# gps.net
KiCad netlist of a schematic drawn in Altium Designer
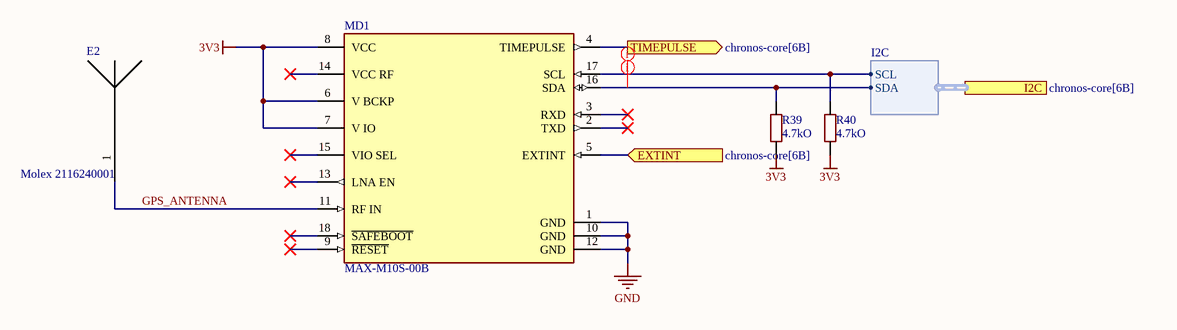
[diagram p0: gps.SchDoc]

(export (version "E")
  (design (tool "Eeschema 10.0.6"))
  (components
    (comp (ref "E2")
      (value "Molex 2116240001")
      (footprint "Molex_GPS_L1_L5_GLONASS_36MM_STACKED_2116240001")
      (libsource (lib "Molex_GPS_L1_L5_GLONASS_36MM_STACKED_2116240001") (part "Molex_GPS_L1_L5_GLONASS_36MM_STACKED_2116240001"))
    )
    (comp (ref "MD1")
      (value "MAX-M10S-00B")
      (footprint "FP-MAX-M10S-00B-MFG")
      (description "GNSS LCC RX, ROM, TCXO, LNA, SAW")
      (libsource (lib "Altium Content Vault") (part "a308a25f00fc71354910191737d199d"))
    )
    (comp (ref "R39")
      (value "4.7kO")
      (footprint "0402WGF4701TCE")
      (fields
        (field (name "JLCPCB PART #") "C25900")
        (field (name "MANUFACTURER PART NUMBER") "0402WGF4701TCE")
        (field (name "MANUFACTURER") "UNI-ROYAL(Uniroyal Elec)")
      )
      (libsource (lib "0402WGF4701TCE") (part "0402WGF4701TCE"))
    )
    (comp (ref "R40")
      (value "4.7kO")
      (footprint "0402WGF4701TCE")
      (fields
        (field (name "JLCPCB PART #") "C25900")
        (field (name "MANUFACTURER PART NUMBER") "0402WGF4701TCE")
        (field (name "MANUFACTURER") "UNI-ROYAL(Uniroyal Elec)")
      )
      (libsource (lib "0402WGF4701TCE") (part "0402WGF4701TCE"))
    )
  )
  (nets
    (net (code "2") (name "/EXTINT") (class "Default")
      (node (ref "MD1") (pin "5") (pinfunction "EXTINT_5") (pintype "input"))
    )
    (net (code "3") (name "/GPS_ANTENNA") (class "Default")
      (node (ref "E2") (pin "1") (pinfunction "ANT_1") (pintype "passive"))
      (node (ref "MD1") (pin "11") (pinfunction "RF_IN_11") (pintype "input"))
    )
    (net (code "4") (name "/TIMEPULSE") (class "Default")
      (node (ref "MD1") (pin "4") (pinfunction "TIMEPULSE_4") (pintype "output"))
    )
    (net (code "6") (name "3V3") (class "Default")
      (node (ref "MD1") (pin "6") (pinfunction "V_BCKP_6") (pintype "power_in"))
      (node (ref "MD1") (pin "7") (pinfunction "V_IO_7") (pintype "power_in"))
      (node (ref "MD1") (pin "8") (pinfunction "VCC_8") (pintype "power_in"))
      (node (ref "R39") (pin "1") (pinfunction "1_1") (pintype "passive"))
      (node (ref "R40") (pin "1") (pinfunction "1_1") (pintype "passive"))
    )
    (net (code "7") (name "GND") (class "Default")
      (node (ref "MD1") (pin "1") (pinfunction "GND_1") (pintype "power_in"))
      (node (ref "MD1") (pin "10") (pinfunction "GND_10") (pintype "power_in"))
      (node (ref "MD1") (pin "12") (pinfunction "GND_12") (pintype "power_in"))
    )
    (net (code "8") (name "Net-(MD1-SCL)") (class "Default")
      (node (ref "MD1") (pin "17") (pinfunction "SCL_17") (pintype "input"))
      (node (ref "R40") (pin "2") (pinfunction "2_2") (pintype "passive"))
    )
    (net (code "9") (name "Net-(MD1-SDA)") (class "Default")
      (node (ref "MD1") (pin "16") (pinfunction "SDA_16") (pintype "bidirectional"))
      (node (ref "R39") (pin "2") (pinfunction "2_2") (pintype "passive"))
    )
    (net (code "10") (name "unconnected-(MD1-LNA_EN-Pad13)") (class "Default")
      (node (ref "MD1") (pin "13") (pinfunction "LNA_EN_13") (pintype "output+no_connect"))
    )
    (net (code "11") (name "unconnected-(MD1-RXD-Pad3)") (class "Default")
      (node (ref "MD1") (pin "3") (pinfunction "RXD_3") (pintype "input+no_connect"))
    )
    (net (code "12") (name "unconnected-(MD1-TXD-Pad2)") (class "Default")
      (node (ref "MD1") (pin "2") (pinfunction "TXD_2") (pintype "output+no_connect"))
    )
    (net (code "13") (name "unconnected-(MD1-VCC_RF-Pad14)") (class "Default")
      (node (ref "MD1") (pin "14") (pinfunction "VCC_RF_14") (pintype "power_in+no_connect"))
    )
    (net (code "14") (name "unconnected-(MD1-VIO_SEL-Pad15)") (class "Default")
      (node (ref "MD1") (pin "15") (pinfunction "VIO_SEL_15") (pintype "power_in+no_connect"))
    )
    (net (code "15") (name "unconnected-(MD1-~{RESET}-Pad9)") (class "Default")
      (node (ref "MD1") (pin "9") (pinfunction "~{RESET}_9") (pintype "input+no_connect"))
    )
    (net (code "16") (name "unconnected-(MD1-~{SAFEBOOT}-Pad18)") (class "Default")
      (node (ref "MD1") (pin "18") (pinfunction "~{SAFEBOOT}_18") (pintype "input+no_connect"))
    )
  )
)
